# rp2040BOY.net
KiCad netlist of a schematic drawn in EAGLE
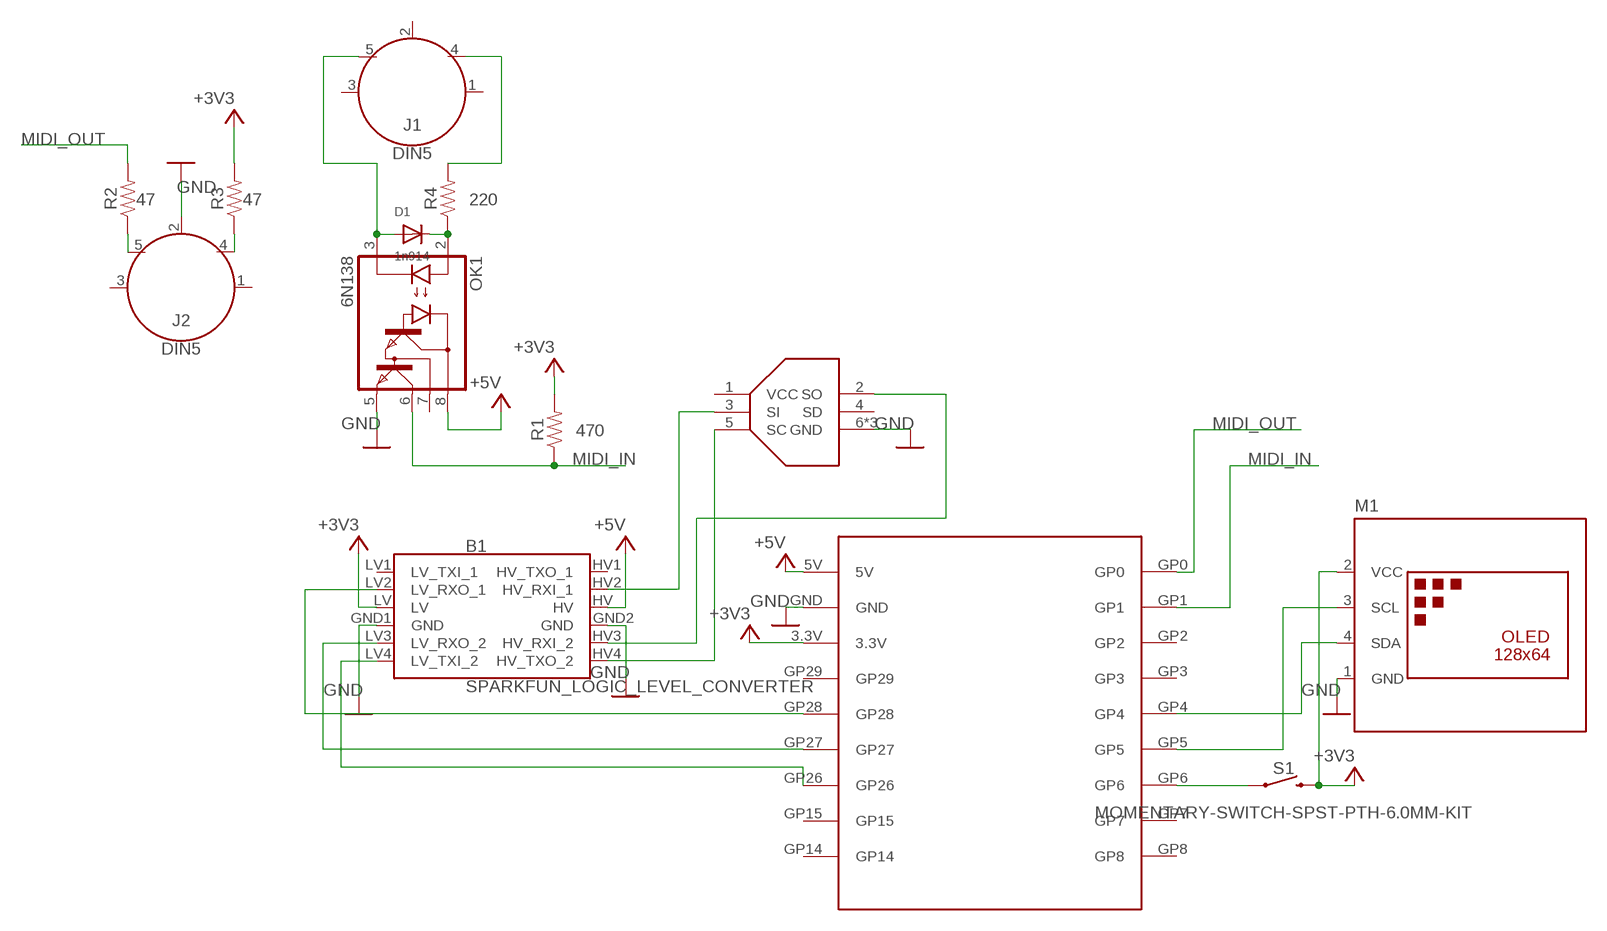
[diagram p0: schematic, sheet 1]

(export (version "E")
  (design (tool "Eeschema 10.0.6"))
  (components
    (comp (ref "B1")
      (value "SPARKFUN_LOGIC_LEVEL_CONVERTER")
      (footprint "eagle-import:SPARKFUN_LOGIC_LEVEL_CONVERTER")
      (libsource (lib "eagle-import") (part "SPARKFUN_LOGIC_LEVEL_CONVERTER"))
    )
    (comp (ref "D1")
      (value "1n914")
      (footprint "eagle-import:DO-1N4148")
      (libsource (lib "eagle-import") (part "DIODEDO-1N4148"))
    )
    (comp (ref "J1")
      (value "DIN5")
      (footprint "eagle-import:DIN5-RA-PTH")
      (libsource (lib "eagle-import") (part "DIN5"))
    )
    (comp (ref "J2")
      (value "DIN5")
      (footprint "eagle-import:DIN5-RA-PTH")
      (libsource (lib "eagle-import") (part "DIN5"))
    )
    (comp (ref "M1")
      (value "OLED-128X64-I2C-NH")
      (footprint "eagle-import:DISPLAY-OLED-128X64-I2C_NH")
      (libsource (lib "eagle-import") (part "OLED-128X64-I2C-NH"))
    )
    (comp (ref "OK1")
      (value "6N138")
      (footprint "eagle-import:DIL08")
      (fields (field (name "MF") "VISHAY/TELEFUNKEN"))
      (libsource (lib "eagle-import") (part "6N138"))
    )
    (comp (ref "R1")
      (value "470")
      (footprint "eagle-import:AXIAL-0.3")
      (libsource (lib "eagle-import") (part "RESISTORAXIAL-0.3"))
    )
    (comp (ref "R2")
      (value "47")
      (footprint "eagle-import:AXIAL-0.3")
      (libsource (lib "eagle-import") (part "RESISTORAXIAL-0.3"))
    )
    (comp (ref "R3")
      (value "47")
      (footprint "eagle-import:AXIAL-0.3")
      (libsource (lib "eagle-import") (part "RESISTORAXIAL-0.3"))
    )
    (comp (ref "R4")
      (value "220")
      (footprint "eagle-import:AXIAL-0.3")
      (libsource (lib "eagle-import") (part "RESISTORAXIAL-0.3"))
    )
    (comp (ref "S1")
      (value "MOMENTARY-SWITCH-SPST-PTH-6.0MM-KIT")
      (footprint "eagle-import:TACTILE_SWITCH_PTH_6.0MM_KIT")
      (libsource (lib "eagle-import") (part "MOMENTARY-SWITCH-SPST-PTH-6.0MM-KIT"))
    )
    (comp (ref "U$1")
      (value "GBC_LINK_CONN")
      (footprint "eagle-import:GBC")
      (libsource (lib "eagle-import") (part "GBC_LINK_CONN"))
    )
    (comp (ref "U$2")
      (value "RP2040-ZERO-ROUND")
      (footprint "eagle-import:RP2040-ZERO_O")
      (libsource (lib "eagle-import") (part "RP2040-ZERO-ROUND"))
    )
  )
  (nets
    (net (code "1") (name "+3V3") (class "Default")
      (node (ref "B1") (pin "LV") (pinfunction "LV_LV") (pintype "power_in"))
      (node (ref "M1") (pin "2") (pinfunction "VCC_2") (pintype "power_in"))
      (node (ref "R1") (pin "P$2") (pinfunction "2_P$2") (pintype "passive"))
      (node (ref "R3") (pin "P$2") (pinfunction "2_P$2") (pintype "passive"))
      (node (ref "S1") (pin "3") (pinfunction "2_3") (pintype "passive"))
      (node (ref "U$2") (pin "3.3V") (pinfunction "3.3V_3.3V") (pintype "bidirectional"))
    )
    (net (code "2") (name "+5V") (class "Default")
      (node (ref "B1") (pin "HV") (pinfunction "HV_HV") (pintype "power_in"))
      (node (ref "OK1") (pin "8") (pinfunction "VCC_8") (pintype "passive"))
      (node (ref "U$2") (pin "5V") (pinfunction "5V_5V") (pintype "bidirectional"))
    )
    (net (code "3") (name "/MIDI_IN") (class "Default")
      (node (ref "OK1") (pin "6") (pinfunction "VO_6") (pintype "passive"))
      (node (ref "R1") (pin "P$1") (pinfunction "1_P$1") (pintype "passive"))
      (node (ref "U$2") (pin "GP1") (pinfunction "GP1_GP1") (pintype "bidirectional"))
    )
    (net (code "4") (name "/MIDI_OUT") (class "Default")
      (node (ref "R2") (pin "P$2") (pinfunction "2_P$2") (pintype "passive"))
      (node (ref "U$2") (pin "GP0") (pinfunction "GP0_GP0") (pintype "bidirectional"))
    )
    (net (code "5") (name "GND") (class "Default")
      (node (ref "B1") (pin "GND1") (pinfunction "GND_GND1") (pintype "power_in"))
      (node (ref "B1") (pin "GND2") (pinfunction "GND_GND2") (pintype "power_in"))
      (node (ref "J2") (pin "2") (pinfunction "2_2") (pintype "bidirectional"))
      (node (ref "M1") (pin "1") (pinfunction "GND_1") (pintype "power_in"))
      (node (ref "OK1") (pin "5") (pinfunction "GND_5") (pintype "passive"))
      (node (ref "U$1") (pin "6") (pinfunction "GND_6") (pintype "bidirectional"))
      (node (ref "U$1") (pin "P$7") (pinfunction "GND_P$7") (pintype "bidirectional"))
      (node (ref "U$1") (pin "P$8") (pinfunction "GND_P$8") (pintype "bidirectional"))
      (node (ref "U$2") (pin "GND") (pinfunction "GND_GND") (pintype "bidirectional"))
    )
    (net (code "6") (name "Net-(B1-HV_RXI_1)") (class "Default")
      (node (ref "B1") (pin "HV2") (pinfunction "HV_RXI_1_HV2") (pintype "bidirectional"))
      (node (ref "U$1") (pin "3") (pinfunction "SI_3") (pintype "bidirectional"))
    )
    (net (code "7") (name "Net-(B1-HV_RXI_2)") (class "Default")
      (node (ref "B1") (pin "HV3") (pinfunction "HV_RXI_2_HV3") (pintype "bidirectional"))
      (node (ref "U$1") (pin "2") (pinfunction "SO_2") (pintype "bidirectional"))
    )
    (net (code "8") (name "Net-(B1-HV_TXO_2)") (class "Default")
      (node (ref "B1") (pin "HV4") (pinfunction "HV_TXO_2_HV4") (pintype "bidirectional"))
      (node (ref "U$1") (pin "5") (pinfunction "SC_5") (pintype "bidirectional"))
    )
    (net (code "9") (name "Net-(B1-LV_RXO_1)") (class "Default")
      (node (ref "B1") (pin "LV2") (pinfunction "LV_RXO_1_LV2") (pintype "bidirectional"))
      (node (ref "U$2") (pin "GP28") (pinfunction "GP28_GP28") (pintype "bidirectional"))
    )
    (net (code "10") (name "Net-(B1-LV_RXO_2)") (class "Default")
      (node (ref "B1") (pin "LV3") (pinfunction "LV_RXO_2_LV3") (pintype "bidirectional"))
      (node (ref "U$2") (pin "GP27") (pinfunction "GP27_GP27") (pintype "bidirectional"))
    )
    (net (code "11") (name "Net-(B1-LV_TXI_2)") (class "Default")
      (node (ref "B1") (pin "LV4") (pinfunction "LV_TXI_2_LV4") (pintype "bidirectional"))
      (node (ref "U$2") (pin "GP26") (pinfunction "GP26_GP26") (pintype "bidirectional"))
    )
    (net (code "12") (name "Net-(M1-SCL)") (class "Default")
      (node (ref "M1") (pin "3") (pinfunction "SCL_3") (pintype "bidirectional"))
      (node (ref "U$2") (pin "GP5") (pinfunction "GP5_GP5") (pintype "bidirectional"))
    )
    (net (code "13") (name "Net-(M1-SDA)") (class "Default")
      (node (ref "M1") (pin "4") (pinfunction "SDA_4") (pintype "bidirectional"))
      (node (ref "U$2") (pin "GP4") (pinfunction "GP4_GP4") (pintype "bidirectional"))
    )
    (net (code "14") (name "Net-(OK1-A)") (class "Default")
      (node (ref "D1") (pin "C") (pinfunction "C_C") (pintype "passive"))
      (node (ref "OK1") (pin "2") (pinfunction "A_2") (pintype "passive"))
      (node (ref "R4") (pin "P$1") (pinfunction "1_P$1") (pintype "passive"))
    )
    (net (code "15") (name "Net-(OK1-C)") (class "Default")
      (node (ref "D1") (pin "A") (pinfunction "A_A") (pintype "passive"))
      (node (ref "J1") (pin "5") (pinfunction "5_5") (pintype "bidirectional"))
      (node (ref "OK1") (pin "3") (pinfunction "C_3") (pintype "passive"))
    )
    (net (code "16") (name "Net-(R2-1)") (class "Default")
      (node (ref "J2") (pin "5") (pinfunction "5_5") (pintype "bidirectional"))
      (node (ref "R2") (pin "P$1") (pinfunction "1_P$1") (pintype "passive"))
    )
    (net (code "17") (name "Net-(R3-1)") (class "Default")
      (node (ref "J2") (pin "4") (pinfunction "4_4") (pintype "bidirectional"))
      (node (ref "R3") (pin "P$1") (pinfunction "1_P$1") (pintype "passive"))
    )
    (net (code "18") (name "Net-(R4-2)") (class "Default")
      (node (ref "J1") (pin "4") (pinfunction "4_4") (pintype "bidirectional"))
      (node (ref "R4") (pin "P$2") (pinfunction "2_P$2") (pintype "passive"))
    )
    (net (code "19") (name "Net-(S1-Pad1)") (class "Default")
      (node (ref "S1") (pin "1") (pinfunction "1_1") (pintype "passive"))
      (node (ref "U$2") (pin "GP6") (pinfunction "GP6_GP6") (pintype "bidirectional"))
    )
    (net (code "20") (name "unconnected-(B1-HV_TXO_1-PadHV1)") (class "Default")
      (node (ref "B1") (pin "HV1") (pinfunction "HV_TXO_1_HV1") (pintype "bidirectional"))
    )
    (net (code "21") (name "unconnected-(B1-LV_TXI_1-PadLV1)") (class "Default")
      (node (ref "B1") (pin "LV1") (pinfunction "LV_TXI_1_LV1") (pintype "bidirectional"))
    )
    (net (code "22") (name "unconnected-(J1-Pad1)") (class "Default")
      (node (ref "J1") (pin "1") (pinfunction "1_1") (pintype "bidirectional"))
    )
    (net (code "23") (name "unconnected-(J1-Pad2)") (class "Default")
      (node (ref "J1") (pin "2") (pinfunction "2_2") (pintype "bidirectional"))
    )
    (net (code "24") (name "unconnected-(J1-Pad3)") (class "Default")
      (node (ref "J1") (pin "3") (pinfunction "3_3") (pintype "bidirectional"))
    )
    (net (code "25") (name "unconnected-(J2-Pad1)") (class "Default")
      (node (ref "J2") (pin "1") (pinfunction "1_1") (pintype "bidirectional"))
    )
    (net (code "26") (name "unconnected-(J2-Pad3)") (class "Default")
      (node (ref "J2") (pin "3") (pinfunction "3_3") (pintype "bidirectional"))
    )
    (net (code "27") (name "unconnected-(OK1-VB-Pad7)") (class "Default")
      (node (ref "OK1") (pin "7") (pinfunction "VB_7") (pintype "passive"))
    )
    (net (code "28") (name "unconnected-(U$1-SD-Pad4)") (class "Default")
      (node (ref "U$1") (pin "4") (pinfunction "SD_4") (pintype "bidirectional"))
    )
    (net (code "29") (name "unconnected-(U$1-VCC-Pad1)") (class "Default")
      (node (ref "U$1") (pin "1") (pinfunction "VCC_1") (pintype "bidirectional"))
    )
    (net (code "30") (name "unconnected-(U$2-PadGP2)") (class "Default")
      (node (ref "U$2") (pin "GP2") (pinfunction "GP2_GP2") (pintype "bidirectional"))
    )
    (net (code "31") (name "unconnected-(U$2-PadGP3)") (class "Default")
      (node (ref "U$2") (pin "GP3") (pinfunction "GP3_GP3") (pintype "bidirectional"))
    )
    (net (code "32") (name "unconnected-(U$2-PadGP7)") (class "Default")
      (node (ref "U$2") (pin "GP7") (pinfunction "GP7_GP7") (pintype "bidirectional"))
    )
    (net (code "33") (name "unconnected-(U$2-PadGP8)") (class "Default")
      (node (ref "U$2") (pin "GP8") (pinfunction "GP8_GP8") (pintype "bidirectional"))
    )
    (net (code "34") (name "unconnected-(U$2-PadGP14)") (class "Default")
      (node (ref "U$2") (pin "GP14") (pinfunction "GP14_GP14") (pintype "bidirectional"))
    )
    (net (code "35") (name "unconnected-(U$2-PadGP15)") (class "Default")
      (node (ref "U$2") (pin "GP15") (pinfunction "GP15_GP15") (pintype "bidirectional"))
    )
    (net (code "36") (name "unconnected-(U$2-PadGP29)") (class "Default")
      (node (ref "U$2") (pin "GP29") (pinfunction "GP29_GP29") (pintype "bidirectional"))
    )
  )
)
